# SCH_ASTRA-Unit00_2024-12-20.net
KiCad netlist of a schematic drawn in EasyEDA
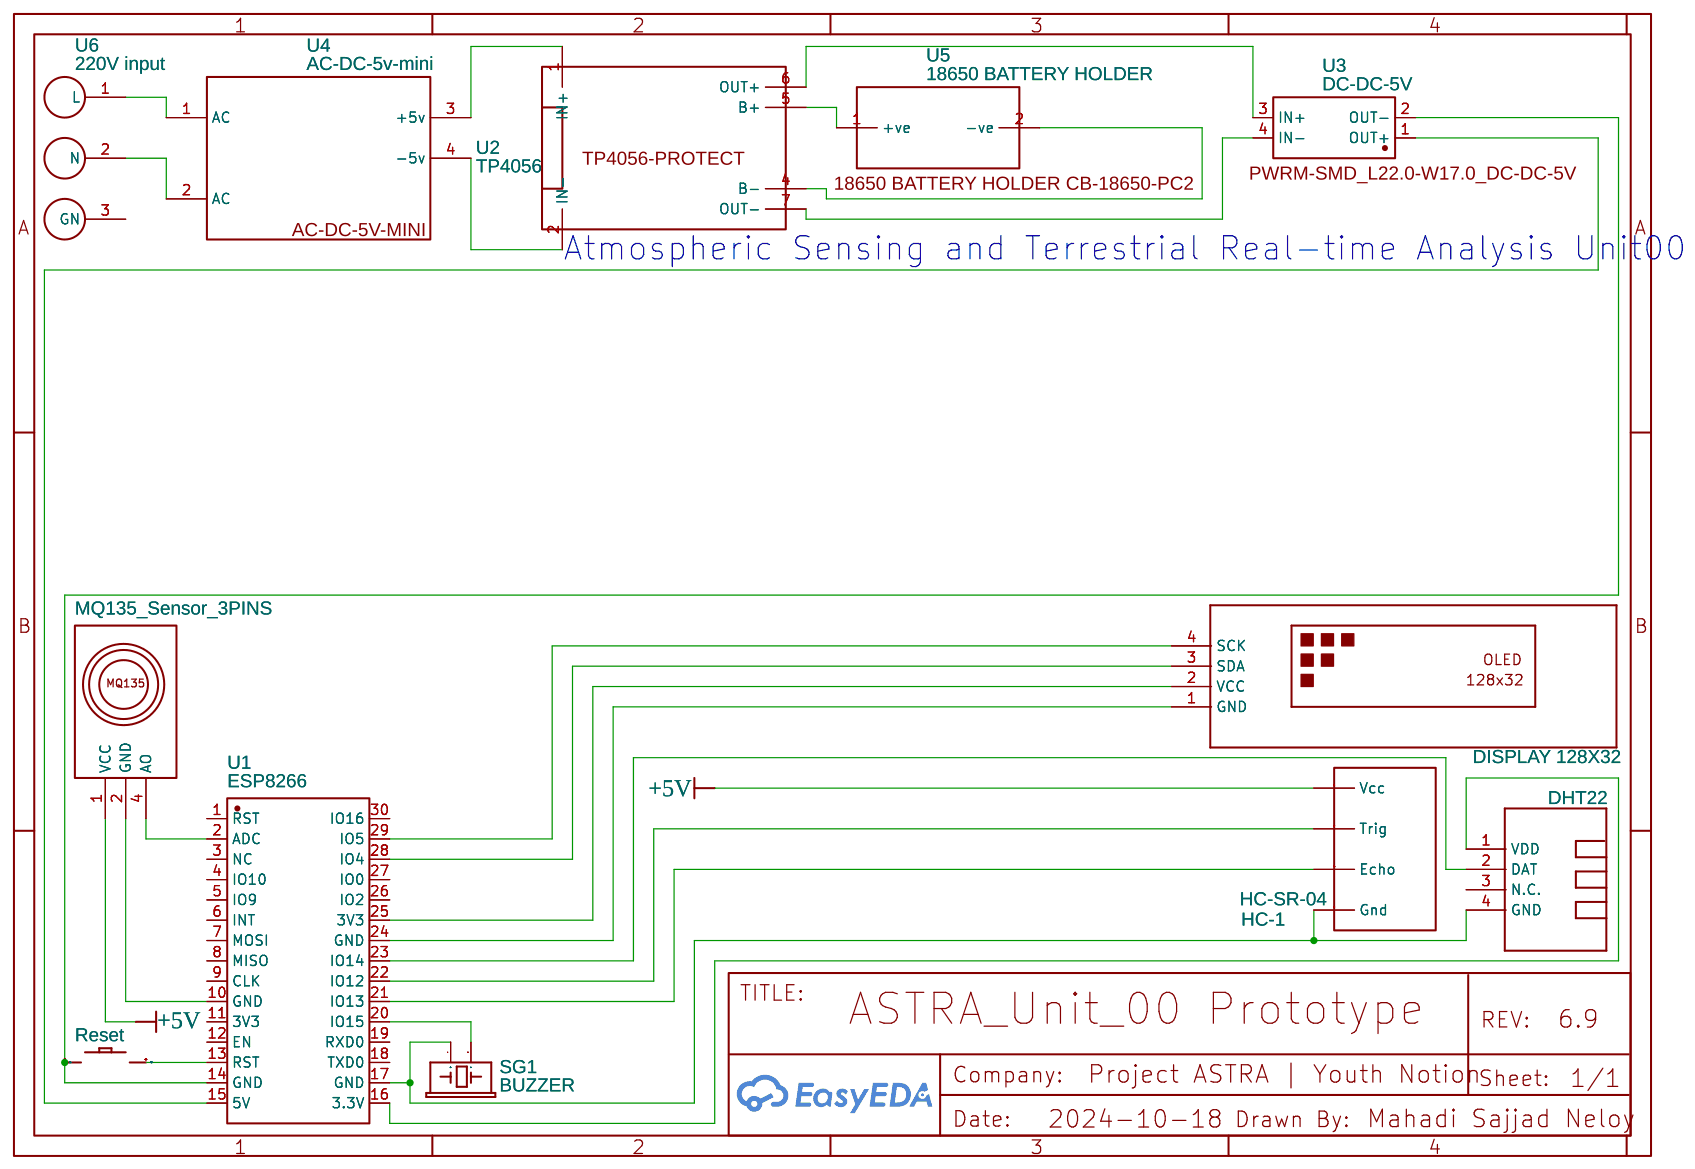
[diagram p0: schematic sheet]

(export (version "E")
  (design (tool "Eeschema 10.0.6"))
  (components
    (comp (ref "1") (value "DISPLAY 128X32") (libsource (lib "") (part "DISPLAY-OLED-128X32")))
    (comp (ref "2") (value "DHT22") (libsource (lib "") (part "TEMP-HUM-SENSOR-DHT22")))
    (comp (ref "3") (value "Reset") (libsource (lib "") (part "button")))
    (comp (ref "HC-1") (value "HC-SR-04") (libsource (lib "") (part "HC-SR-04")))
    (comp (ref "SG1") (value "BUZZER") (libsource (lib "") (part "BUZZER")))
    (comp (ref "U1")
      (value "ESP8266")
      (fields
        (field (name "Manufacturer Part") "NODEMCU(12F)")
        (field (name "Manufacturer") "Ai-Thinker(安信可)")
      )
      (libsource (lib "") (part "NODEMCU(12F)"))
    )
    (comp (ref "U2")
      (value "TP4056")
      (fields (field (name "Manufacturer Part") "TP4056-protect"))
      (libsource (lib "") (part "TP4056"))
    )
    (comp (ref "U3") (value "DC-DC-5V") (libsource (lib "") (part "DC-DC-5V")))
    (comp (ref "U4") (value "AC-DC-5v-mini") (libsource (lib "") (part "AC-DC-5v-mini")))
    (comp (ref "U5")
      (value "18650 BATTERY HOLDER")
      (libsource (lib "") (part "18650 BATTERY HOLDER CB-18650-PC2 _NOTEMP COPY"))
    )
    (comp (ref "U6") (value "220V input") (libsource (lib "") (part "220V input")))
    (comp (ref "U7") (value "MQ135_Sensor_3PINS") (libsource (lib "") (part "MQ135_Sensor_3PINS")))
  )
  (nets
    (net (code "1") (name "+5V") (class "Default")
      (node (ref "HC-1") (pin "VCC") (pinfunction "Vcc_VCC") (pintype "unspecified"))
      (node (ref "U7") (pin "1") (pinfunction "VCC_1") (pintype "unspecified"))
    )
    (net (code "2") (name "Net-(1-GND)") (class "Default")
      (node (ref "1") (pin "1") (pinfunction "GND_1") (pintype "bidirectional"))
      (node (ref "U1") (pin "24") (pinfunction "GND_24") (pintype "unspecified"))
    )
    (net (code "3") (name "Net-(1-SCK)") (class "Default")
      (node (ref "1") (pin "4") (pinfunction "SCK_4") (pintype "bidirectional"))
      (node (ref "U1") (pin "29") (pinfunction "IO5_29") (pintype "unspecified"))
    )
    (net (code "4") (name "Net-(1-SDA)") (class "Default")
      (node (ref "1") (pin "3") (pinfunction "SDA_3") (pintype "bidirectional"))
      (node (ref "U1") (pin "28") (pinfunction "IO4_28") (pintype "unspecified"))
    )
    (net (code "5") (name "Net-(1-VCC)") (class "Default")
      (node (ref "1") (pin "2") (pinfunction "VCC_2") (pintype "bidirectional"))
      (node (ref "U1") (pin "25") (pinfunction "3V3_25") (pintype "unspecified"))
    )
    (net (code "6") (name "Net-(2-DAT)") (class "Default")
      (node (ref "2") (pin "2") (pinfunction "DAT_2") (pintype "bidirectional"))
      (node (ref "U1") (pin "23") (pinfunction "IO14_23") (pintype "unspecified"))
    )
    (net (code "7") (name "Net-(2-GND)") (class "Default")
      (node (ref "2") (pin "4") (pinfunction "GND_4") (pintype "bidirectional"))
      (node (ref "HC-1") (pin "GND") (pinfunction "Gnd_GND") (pintype "unspecified"))
      (node (ref "SG1") (pin "-") (pinfunction "2_-") (pintype "unspecified"))
      (node (ref "U1") (pin "17") (pinfunction "GND_17") (pintype "unspecified"))
    )
    (net (code "8") (name "Net-(2-VDD)") (class "Default")
      (node (ref "2") (pin "1") (pinfunction "VDD_1") (pintype "bidirectional"))
      (node (ref "U1") (pin "16") (pinfunction "3.3V_16") (pintype "unspecified"))
    )
    (net (code "9") (name "Net-(3-PadP$ACTIVE)") (class "Default")
      (node (ref "3") (pin "P$ACTIVE") (pinfunction "P$ACTIVE_P$ACTIVE") (pintype "unspecified"))
      (node (ref "U1") (pin "13") (pinfunction "RST_13") (pintype "unspecified"))
    )
    (net (code "10") (name "Net-(HC-1-Echo)") (class "Default")
      (node (ref "HC-1") (pin "ECHO") (pinfunction "Echo_ECHO") (pintype "unspecified"))
      (node (ref "U1") (pin "21") (pinfunction "IO13_21") (pintype "unspecified"))
    )
    (net (code "11") (name "Net-(HC-1-Trig)") (class "Default")
      (node (ref "HC-1") (pin "TRIG") (pinfunction "Trig_TRIG") (pintype "unspecified"))
      (node (ref "U1") (pin "22") (pinfunction "IO12_22") (pintype "unspecified"))
    )
    (net (code "12") (name "Net-(SG1-1)") (class "Default")
      (node (ref "SG1") (pin "+") (pinfunction "1_+") (pintype "unspecified"))
      (node (ref "U1") (pin "20") (pinfunction "IO15_20") (pintype "unspecified"))
    )
    (net (code "13") (name "Net-(U1-5V)") (class "Default")
      (node (ref "U1") (pin "15") (pinfunction "5V_15") (pintype "unspecified"))
      (node (ref "U3") (pin "1") (pinfunction "OUT+_1") (pintype "unspecified"))
    )
    (net (code "14") (name "Net-(U1-ADC)") (class "Default")
      (node (ref "U1") (pin "2") (pinfunction "ADC_2") (pintype "unspecified"))
      (node (ref "U7") (pin "4") (pinfunction "AO_4") (pintype "unspecified"))
    )
    (net (code "15") (name "Net-(U2-B+)") (class "Default")
      (node (ref "U2") (pin "5") (pinfunction "B+_5") (pintype "unspecified"))
      (node (ref "U5") (pin "1") (pinfunction "+ve_1") (pintype "unspecified"))
    )
    (net (code "16") (name "Net-(U2-B-)") (class "Default")
      (node (ref "U2") (pin "4") (pinfunction "B-_4") (pintype "unspecified"))
      (node (ref "U5") (pin "2") (pinfunction "-ve_2") (pintype "unspecified"))
    )
    (net (code "17") (name "Net-(U2-IN+)") (class "Default")
      (node (ref "U2") (pin "1") (pinfunction "IN+_1") (pintype "unspecified"))
      (node (ref "U4") (pin "3") (pinfunction "+5v_3") (pintype "unspecified"))
    )
    (net (code "18") (name "Net-(U2-IN-)") (class "Default")
      (node (ref "U2") (pin "2") (pinfunction "IN-_2") (pintype "unspecified"))
      (node (ref "U4") (pin "4") (pinfunction "-5v_4") (pintype "unspecified"))
    )
    (net (code "19") (name "Net-(U2-OUT+)") (class "Default")
      (node (ref "U2") (pin "6") (pinfunction "OUT+_6") (pintype "unspecified"))
      (node (ref "U3") (pin "3") (pinfunction "IN+_3") (pintype "unspecified"))
    )
    (net (code "20") (name "Net-(U2-OUT-)") (class "Default")
      (node (ref "U2") (pin "7") (pinfunction "OUT-_7") (pintype "unspecified"))
      (node (ref "U3") (pin "4") (pinfunction "IN-_4") (pintype "unspecified"))
    )
    (net (code "21") (name "Net-(U3-OUT-)") (class "Default")
      (node (ref "3") (pin "P$GND") (pinfunction "P$GND_P$GND") (pintype "unspecified"))
      (node (ref "U1") (pin "14") (pinfunction "GND_14") (pintype "unspecified"))
      (node (ref "U3") (pin "2") (pinfunction "OUT-_2") (pintype "unspecified"))
    )
    (net (code "22") (name "Net-(U6-L)") (class "Default")
      (node (ref "U4") (pin "1") (pinfunction "AC_1") (pintype "unspecified"))
      (node (ref "U6") (pin "1") (pinfunction "L_1") (pintype "unspecified"))
    )
    (net (code "23") (name "Net-(U6-N)") (class "Default")
      (node (ref "U4") (pin "2") (pinfunction "AC_2") (pintype "unspecified"))
      (node (ref "U6") (pin "2") (pinfunction "N_2") (pintype "unspecified"))
    )
    (net (code "24") (name "Net-(U7-GND)") (class "Default")
      (node (ref "U1") (pin "10") (pinfunction "GND_10") (pintype "unspecified"))
      (node (ref "U7") (pin "2") (pinfunction "GND_2") (pintype "unspecified"))
    )
    (net (code "25") (name "unconnected-(2-N.C.-Pad3)") (class "Default")
      (node (ref "2") (pin "3") (pinfunction "N.C._3") (pintype "bidirectional"))
    )
    (net (code "26") (name "unconnected-(U1-3V3-Pad11)") (class "Default")
      (node (ref "U1") (pin "11") (pinfunction "3V3_11") (pintype "unspecified"))
    )
    (net (code "27") (name "unconnected-(U1-CLK-Pad9)") (class "Default")
      (node (ref "U1") (pin "9") (pinfunction "CLK_9") (pintype "unspecified"))
    )
    (net (code "28") (name "unconnected-(U1-EN-Pad12)") (class "Default")
      (node (ref "U1") (pin "12") (pinfunction "EN_12") (pintype "unspecified"))
    )
    (net (code "29") (name "unconnected-(U1-INT-Pad6)") (class "Default")
      (node (ref "U1") (pin "6") (pinfunction "INT_6") (pintype "unspecified"))
    )
    (net (code "30") (name "unconnected-(U1-IO0-Pad27)") (class "Default")
      (node (ref "U1") (pin "27") (pinfunction "IO0_27") (pintype "unspecified"))
    )
    (net (code "31") (name "unconnected-(U1-IO2-Pad26)") (class "Default")
      (node (ref "U1") (pin "26") (pinfunction "IO2_26") (pintype "unspecified"))
    )
    (net (code "32") (name "unconnected-(U1-IO9-Pad5)") (class "Default")
      (node (ref "U1") (pin "5") (pinfunction "IO9_5") (pintype "unspecified"))
    )
    (net (code "33") (name "unconnected-(U1-IO10-Pad4)") (class "Default")
      (node (ref "U1") (pin "4") (pinfunction "IO10_4") (pintype "unspecified"))
    )
    (net (code "34") (name "unconnected-(U1-IO16-Pad30)") (class "Default")
      (node (ref "U1") (pin "30") (pinfunction "IO16_30") (pintype "unspecified"))
    )
    (net (code "35") (name "unconnected-(U1-MISO-Pad8)") (class "Default")
      (node (ref "U1") (pin "8") (pinfunction "MISO_8") (pintype "unspecified"))
    )
    (net (code "36") (name "unconnected-(U1-MOSI-Pad7)") (class "Default")
      (node (ref "U1") (pin "7") (pinfunction "MOSI_7") (pintype "unspecified"))
    )
    (net (code "37") (name "unconnected-(U1-NC-Pad3)") (class "Default")
      (node (ref "U1") (pin "3") (pinfunction "NC_3") (pintype "unspecified"))
    )
    (net (code "38") (name "unconnected-(U1-RST-Pad1)") (class "Default")
      (node (ref "U1") (pin "1") (pinfunction "RST_1") (pintype "unspecified"))
    )
    (net (code "39") (name "unconnected-(U1-RXD0-Pad19)") (class "Default")
      (node (ref "U1") (pin "19") (pinfunction "RXD0_19") (pintype "unspecified"))
    )
    (net (code "40") (name "unconnected-(U1-TXD0-Pad18)") (class "Default")
      (node (ref "U1") (pin "18") (pinfunction "TXD0_18") (pintype "unspecified"))
    )
    (net (code "41") (name "unconnected-(U6-GN-Pad3)") (class "Default")
      (node (ref "U6") (pin "3") (pinfunction "GN_3") (pintype "unspecified"))
    )
  )
)
